# v4MetroKnome.net
KiCad netlist of a schematic drawn in EAGLE
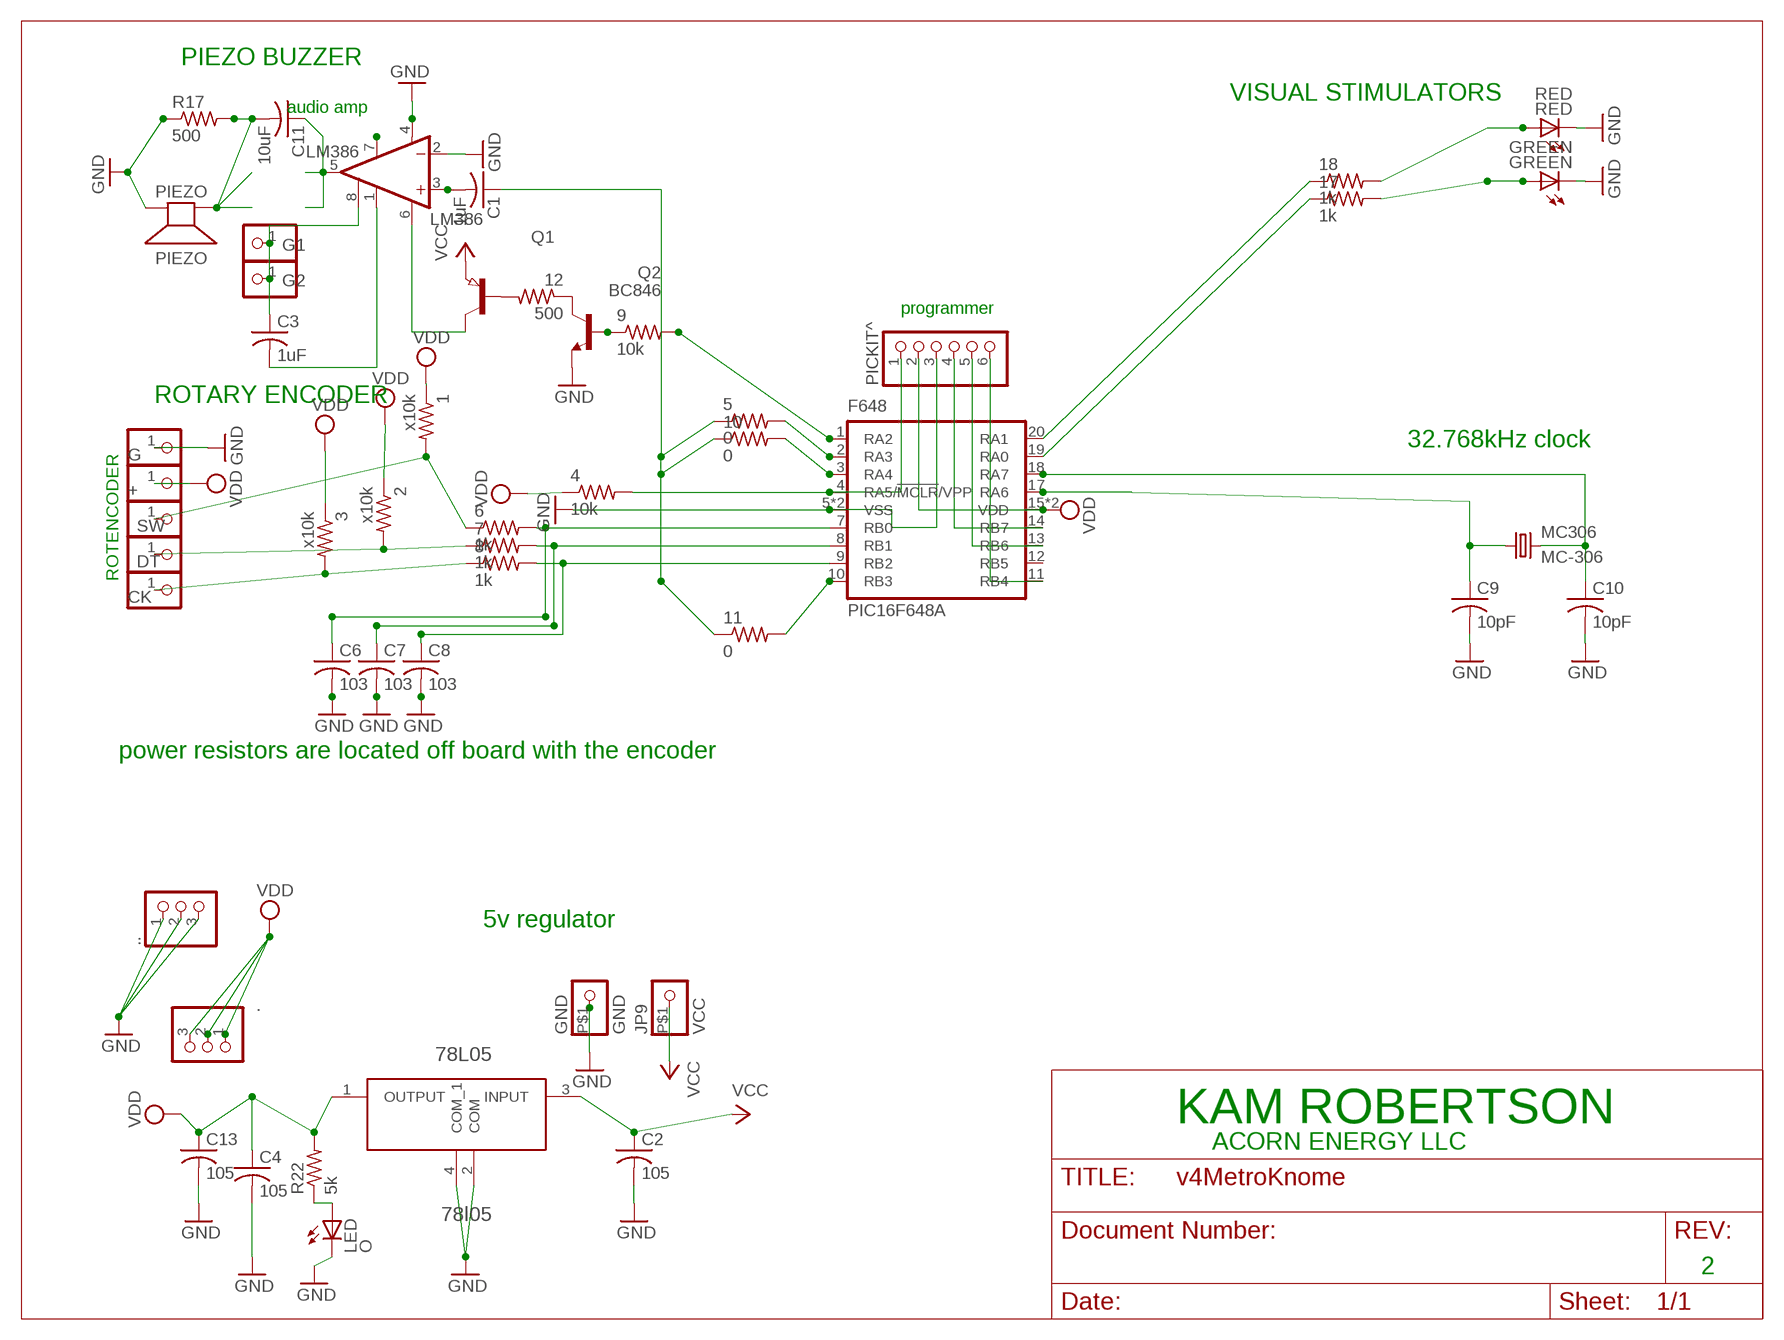
[diagram p0: schematic, sheet 1]

(export (version "E")
  (design (tool "Eeschema 10.0.6"))
  (components
    (comp (ref "+")
      (value "PINHD-1X1CB")
      (footprint "eagle-import:1X01-CLEANBIG")
      (libsource (lib "eagle-import") (part "PINHD-1X1CB"))
    )
    (comp (ref ".")
      (value "PINHD-1X3CB")
      (footprint "eagle-import:1X03-CLEANBIG")
      (libsource (lib "eagle-import") (part "PINHD-1X3CB"))
    )
    (comp (ref "..")
      (value "PINHD-1X3CB")
      (footprint "eagle-import:1X03-CLEANBIG")
      (libsource (lib "eagle-import") (part "PINHD-1X3CB"))
    )
    (comp (ref "1")
      (value "x10k")
      (footprint "eagle-import:R1206")
      (libsource (lib "eagle-import") (part "R-US_R1206"))
    )
    (comp (ref "2")
      (value "x10k")
      (footprint "eagle-import:R1206")
      (libsource (lib "eagle-import") (part "R-US_R1206"))
    )
    (comp (ref "3")
      (value "x10k")
      (footprint "eagle-import:R1206")
      (libsource (lib "eagle-import") (part "R-US_R1206"))
    )
    (comp (ref "4")
      (value "10k")
      (footprint "eagle-import:R1206")
      (libsource (lib "eagle-import") (part "R-US_R1206"))
    )
    (comp (ref "5")
      (value "0")
      (footprint "eagle-import:R1206")
      (libsource (lib "eagle-import") (part "R-US_R1206"))
    )
    (comp (ref "6")
      (value "1k")
      (footprint "eagle-import:R1206")
      (libsource (lib "eagle-import") (part "R-US_R1206"))
    )
    (comp (ref "7")
      (value "1k")
      (footprint "eagle-import:R1206")
      (libsource (lib "eagle-import") (part "R-US_R1206"))
    )
    (comp (ref "8")
      (value "1k")
      (footprint "eagle-import:R1206")
      (libsource (lib "eagle-import") (part "R-US_R1206"))
    )
    (comp (ref "9")
      (value "10k")
      (footprint "eagle-import:R1206")
      (libsource (lib "eagle-import") (part "R-US_R1206"))
    )
    (comp (ref "10")
      (value "0")
      (footprint "eagle-import:R1206")
      (libsource (lib "eagle-import") (part "R-US_R1206"))
    )
    (comp (ref "11")
      (value "0")
      (footprint "eagle-import:R1206")
      (libsource (lib "eagle-import") (part "R-US_R1206"))
    )
    (comp (ref "12")
      (value "500")
      (footprint "eagle-import:R1206")
      (libsource (lib "eagle-import") (part "R-US_R1206"))
    )
    (comp (ref "17")
      (value "1k")
      (footprint "eagle-import:R1206")
      (libsource (lib "eagle-import") (part "R-US_R1206"))
    )
    (comp (ref "18")
      (value "1k")
      (footprint "eagle-import:R1206")
      (libsource (lib "eagle-import") (part "R-US_R1206"))
    )
    (comp (ref "78L05")
      (value "78l05")
      (footprint "eagle-import:SOT150P400X160-4N")
      (fields (field (name "MPN") "UA78L05ACPKG3"))
      (libsource (lib "eagle-import") (part "UA78L05ACPKG3"))
    )
    (comp (ref "C1")
      (value "1uF")
      (footprint "eagle-import:C1210")
      (libsource (lib "eagle-import") (part "C-USC1210"))
    )
    (comp (ref "C2")
      (value "105")
      (footprint "eagle-import:C1210")
      (libsource (lib "eagle-import") (part "C-USC1210"))
    )
    (comp (ref "C3")
      (value "1uF")
      (footprint "eagle-import:C1210")
      (libsource (lib "eagle-import") (part "C-USC1210"))
    )
    (comp (ref "C4")
      (value "105")
      (footprint "eagle-import:C1210")
      (libsource (lib "eagle-import") (part "C-USC1210"))
    )
    (comp (ref "C6")
      (value "103")
      (footprint "eagle-import:C1210")
      (libsource (lib "eagle-import") (part "C-USC1210"))
    )
    (comp (ref "C7")
      (value "103")
      (footprint "eagle-import:C1210")
      (libsource (lib "eagle-import") (part "C-USC1210"))
    )
    (comp (ref "C8")
      (value "103")
      (footprint "eagle-import:C1210")
      (libsource (lib "eagle-import") (part "C-USC1210"))
    )
    (comp (ref "C9")
      (value "10pF")
      (footprint "eagle-import:C1210")
      (libsource (lib "eagle-import") (part "C-USC1210"))
    )
    (comp (ref "C10")
      (value "10pF")
      (footprint "eagle-import:C1210")
      (libsource (lib "eagle-import") (part "C-USC1210"))
    )
    (comp (ref "C11")
      (value "10uF")
      (footprint "eagle-import:C1210")
      (libsource (lib "eagle-import") (part "C-USC1210"))
    )
    (comp (ref "C13")
      (value "105")
      (footprint "eagle-import:C1210")
      (libsource (lib "eagle-import") (part "C-USC1210"))
    )
    (comp (ref "CK")
      (value "PINHD-1X1CB")
      (footprint "eagle-import:1X01-CLEANBIG")
      (libsource (lib "eagle-import") (part "PINHD-1X1CB"))
    )
    (comp (ref "DT")
      (value "PINHD-1X1CB")
      (footprint "eagle-import:1X01-CLEANBIG")
      (libsource (lib "eagle-import") (part "PINHD-1X1CB"))
    )
    (comp (ref "F648")
      (value "PIC16F648A")
      (footprint "eagle-import:SSOP20")
      (libsource (lib "eagle-import") (part "PIC16F1826/27SS"))
    )
    (comp (ref "G")
      (value "PINHD-1X1CB")
      (footprint "eagle-import:1X01-CLEANBIG")
      (libsource (lib "eagle-import") (part "PINHD-1X1CB"))
    )
    (comp (ref "G1")
      (value "PINHD-1X1CB")
      (footprint "eagle-import:1X01-CLEANBIG")
      (libsource (lib "eagle-import") (part "PINHD-1X1CB"))
    )
    (comp (ref "G2")
      (value "PINHD-1X1CB")
      (footprint "eagle-import:1X01-CLEANBIG")
      (libsource (lib "eagle-import") (part "PINHD-1X1CB"))
    )
    (comp (ref "GND")
      (value "GND")
      (footprint "eagle-import:1X1-BIGPOGO")
      (libsource (lib "eagle-import") (part "PINHD-1X1-BIGPOGO"))
    )
    (comp (ref "GREEN")
      (value "GREEN")
      (footprint "eagle-import:LED5MM")
      (libsource (lib "eagle-import") (part "LED5MM"))
    )
    (comp (ref "JP9")
      (value "VCC")
      (footprint "eagle-import:1X1-BIGPOGO")
      (libsource (lib "eagle-import") (part "PINHD-1X1-BIGPOGO"))
    )
    (comp (ref "LED")
      (value "O")
      (footprint "eagle-import:CHIPLED_1206")
      (libsource (lib "eagle-import") (part "LEDCHIPLED_1206"))
    )
    (comp (ref "LM386")
      (value "LM386")
      (footprint "eagle-import:SO08")
      (libsource (lib "eagle-import") (part "LM386?-M1"))
    )
    (comp (ref "MC306")
      (value "MC-306")
      (footprint "eagle-import:MC-306")
      (fields
        (field (name "MPN") "MC-306 60.0KHZ  100PPM ,12.5PF")
        (field (name "MPN_1") "MC-306 60.0KHZ  100PPM ,12.5PF")
        (field (name "OC_FARNELL") "1278040")
        (field (name "OC_NEWARK") "31M5576")
      )
      (libsource (lib "eagle-import") (part "MC-306"))
    )
    (comp (ref "PICKIT^")
      (value "PINHD-1X6LOCK")
      (footprint "eagle-import:1X06-BIGLOCK")
      (libsource (lib "eagle-import") (part "PINHD-1X6LOCK"))
    )
    (comp (ref "PIEZO")
      (value "PIEZO")
      (footprint "eagle-import:PS12")
      (libsource (lib "eagle-import") (part "SPEAKER/PS12"))
    )
    (comp (ref "Q1")
      (value "PNP-TRANSISTOR_SOT89")
      (footprint "eagle-import:SOT89")
      (libsource (lib "eagle-import") (part "PNP-TRANSISTOR_SOT89"))
    )
    (comp (ref "Q2")
      (value "BC846")
      (footprint "eagle-import:SOT23")
      (libsource (lib "eagle-import") (part "BC846"))
    )
    (comp (ref "R17")
      (value "500")
      (footprint "eagle-import:R1206")
      (libsource (lib "eagle-import") (part "R-US_R1206"))
    )
    (comp (ref "R22")
      (value "5k")
      (footprint "eagle-import:R1206")
      (libsource (lib "eagle-import") (part "R-US_R1206"))
    )
    (comp (ref "RED")
      (value "RED")
      (footprint "eagle-import:LED5MM")
      (libsource (lib "eagle-import") (part "LED5MM"))
    )
    (comp (ref "SW")
      (value "PINHD-1X1CB")
      (footprint "eagle-import:1X01-CLEANBIG")
      (libsource (lib "eagle-import") (part "PINHD-1X1CB"))
    )
  )
  (nets
    (net (code "1") (name "GND") (class "Default")
      (node (ref "..") (pin "1") (pinfunction "1_1") (pintype "passive"))
      (node (ref "..") (pin "2") (pinfunction "2_2") (pintype "passive"))
      (node (ref "..") (pin "3") (pinfunction "3_3") (pintype "passive"))
      (node (ref "78L05") (pin "2") (pinfunction "COM_2") (pintype "power_in"))
      (node (ref "78L05") (pin "4") (pinfunction "COM_1_4") (pintype "power_in"))
      (node (ref "C10") (pin "2") (pinfunction "2_2") (pintype "passive"))
      (node (ref "C13") (pin "2") (pinfunction "2_2") (pintype "passive"))
      (node (ref "C2") (pin "2") (pinfunction "2_2") (pintype "passive"))
      (node (ref "C4") (pin "2") (pinfunction "2_2") (pintype "passive"))
      (node (ref "C6") (pin "2") (pinfunction "2_2") (pintype "passive"))
      (node (ref "C7") (pin "2") (pinfunction "2_2") (pintype "passive"))
      (node (ref "C8") (pin "2") (pinfunction "2_2") (pintype "passive"))
      (node (ref "C9") (pin "2") (pinfunction "2_2") (pintype "passive"))
      (node (ref "F648") (pin "5") (pinfunction "VSS_5") (pintype "power_in"))
      (node (ref "F648") (pin "6") (pinfunction "VSS_6") (pintype "power_in"))
      (node (ref "G") (pin "1") (pinfunction "1_1") (pintype "passive"))
      (node (ref "GND") (pin "P$1") (pinfunction "1_P$1") (pintype "passive"))
      (node (ref "GREEN") (pin "K") (pinfunction "C_K") (pintype "passive"))
      (node (ref "LED") (pin "C") (pinfunction "C_C") (pintype "passive"))
      (node (ref "LM386") (pin "2") (pinfunction "-IN_2") (pintype "input"))
      (node (ref "LM386") (pin "4") (pinfunction "GND_4") (pintype "power_in"))
      (node (ref "PICKIT^") (pin "3") (pinfunction "3_3") (pintype "passive"))
      (node (ref "PIEZO") (pin "P$2") (pinfunction "-_P$2") (pintype "passive"))
      (node (ref "Q2") (pin "2") (pinfunction "E_2") (pintype "passive"))
      (node (ref "R17") (pin "1") (pinfunction "1_1") (pintype "passive"))
      (node (ref "RED") (pin "K") (pinfunction "C_K") (pintype "passive"))
    )
    (net (code "2") (name "Net-(1-Pad2)") (class "Default")
      (node (ref "1") (pin "2") (pinfunction "2_2") (pintype "passive"))
      (node (ref "6") (pin "1") (pinfunction "1_1") (pintype "passive"))
      (node (ref "SW") (pin "1") (pinfunction "1_1") (pintype "passive"))
    )
    (net (code "3") (name "Net-(2-Pad2)") (class "Default")
      (node (ref "2") (pin "2") (pinfunction "2_2") (pintype "passive"))
      (node (ref "7") (pin "1") (pinfunction "1_1") (pintype "passive"))
      (node (ref "DT") (pin "1") (pinfunction "1_1") (pintype "passive"))
    )
    (net (code "4") (name "Net-(3-Pad2)") (class "Default")
      (node (ref "3") (pin "2") (pinfunction "2_2") (pintype "passive"))
      (node (ref "8") (pin "1") (pinfunction "1_1") (pintype "passive"))
      (node (ref "CK") (pin "1") (pinfunction "1_1") (pintype "passive"))
    )
    (net (code "5") (name "Net-(10-Pad1)") (class "Default")
      (node (ref "10") (pin "1") (pinfunction "1_1") (pintype "passive"))
      (node (ref "11") (pin "1") (pinfunction "1_1") (pintype "passive"))
      (node (ref "5") (pin "1") (pinfunction "1_1") (pintype "passive"))
      (node (ref "C1") (pin "1") (pinfunction "1_1") (pintype "passive"))
    )
    (net (code "6") (name "Net-(17-Pad2)") (class "Default")
      (node (ref "17") (pin "2") (pinfunction "2_2") (pintype "passive"))
      (node (ref "GREEN") (pin "A") (pinfunction "A_A") (pintype "passive"))
    )
    (net (code "7") (name "Net-(18-Pad2)") (class "Default")
      (node (ref "18") (pin "2") (pinfunction "2_2") (pintype "passive"))
      (node (ref "RED") (pin "A") (pinfunction "A_A") (pintype "passive"))
    )
    (net (code "8") (name "Net-(C3-Pad1)") (class "Default")
      (node (ref "C3") (pin "1") (pinfunction "1_1") (pintype "passive"))
      (node (ref "G1") (pin "1") (pinfunction "1_1") (pintype "passive"))
      (node (ref "G2") (pin "1") (pinfunction "1_1") (pintype "passive"))
      (node (ref "LM386") (pin "8") (pinfunction "GAIN_8") (pintype "passive"))
    )
    (net (code "9") (name "Net-(C3-Pad2)") (class "Default")
      (node (ref "C3") (pin "2") (pinfunction "2_2") (pintype "passive"))
      (node (ref "LM386") (pin "1") (pinfunction "GAIN_1") (pintype "passive"))
    )
    (net (code "10") (name "Net-(F648-RA0)") (class "Default")
      (node (ref "17") (pin "1") (pinfunction "1_1") (pintype "passive"))
      (node (ref "F648") (pin "19") (pinfunction "RA0_19") (pintype "bidirectional"))
    )
    (net (code "11") (name "Net-(F648-RA1)") (class "Default")
      (node (ref "18") (pin "1") (pinfunction "1_1") (pintype "passive"))
      (node (ref "F648") (pin "20") (pinfunction "RA1_20") (pintype "bidirectional"))
    )
    (net (code "12") (name "Net-(F648-RA2)") (class "Default")
      (node (ref "9") (pin "2") (pinfunction "2_2") (pintype "passive"))
      (node (ref "F648") (pin "1") (pinfunction "RA2_1") (pintype "bidirectional"))
    )
    (net (code "13") (name "Net-(F648-RA3)") (class "Default")
      (node (ref "5") (pin "2") (pinfunction "2_2") (pintype "passive"))
      (node (ref "F648") (pin "2") (pinfunction "RA3_2") (pintype "bidirectional"))
    )
    (net (code "14") (name "Net-(F648-RA4)") (class "Default")
      (node (ref "10") (pin "2") (pinfunction "2_2") (pintype "passive"))
      (node (ref "F648") (pin "3") (pinfunction "RA4_3") (pintype "bidirectional"))
    )
    (net (code "15") (name "Net-(F648-RA5{slash}~{MCLR}{slash}VPP)") (class "Default")
      (node (ref "4") (pin "2") (pinfunction "2_2") (pintype "passive"))
      (node (ref "F648") (pin "4") (pinfunction "RA5/~{MCLR}/VPP_4") (pintype "bidirectional"))
      (node (ref "PICKIT^") (pin "1") (pinfunction "1_1") (pintype "passive"))
    )
    (net (code "16") (name "Net-(F648-RA6)") (class "Default")
      (node (ref "C9") (pin "1") (pinfunction "1_1") (pintype "passive"))
      (node (ref "F648") (pin "17") (pinfunction "RA6_17") (pintype "bidirectional"))
      (node (ref "MC306") (pin "1") (pinfunction "1_1") (pintype "passive"))
    )
    (net (code "17") (name "Net-(F648-RA7)") (class "Default")
      (node (ref "C10") (pin "1") (pinfunction "1_1") (pintype "passive"))
      (node (ref "F648") (pin "18") (pinfunction "RA7_18") (pintype "bidirectional"))
      (node (ref "MC306") (pin "4") (pinfunction "2_4") (pintype "passive"))
    )
    (net (code "18") (name "Net-(F648-RB0)") (class "Default")
      (node (ref "6") (pin "2") (pinfunction "2_2") (pintype "passive"))
      (node (ref "C6") (pin "1") (pinfunction "1_1") (pintype "passive"))
      (node (ref "F648") (pin "7") (pinfunction "RB0_7") (pintype "bidirectional"))
    )
    (net (code "19") (name "Net-(F648-RB1)") (class "Default")
      (node (ref "7") (pin "2") (pinfunction "2_2") (pintype "passive"))
      (node (ref "C7") (pin "1") (pinfunction "1_1") (pintype "passive"))
      (node (ref "F648") (pin "8") (pinfunction "RB1_8") (pintype "bidirectional"))
    )
    (net (code "20") (name "Net-(F648-RB2)") (class "Default")
      (node (ref "8") (pin "2") (pinfunction "2_2") (pintype "passive"))
      (node (ref "C8") (pin "1") (pinfunction "1_1") (pintype "passive"))
      (node (ref "F648") (pin "9") (pinfunction "RB2_9") (pintype "bidirectional"))
    )
    (net (code "21") (name "Net-(F648-RB3)") (class "Default")
      (node (ref "11") (pin "2") (pinfunction "2_2") (pintype "passive"))
      (node (ref "F648") (pin "10") (pinfunction "RB3_10") (pintype "bidirectional"))
    )
    (net (code "22") (name "Net-(F648-RB4)") (class "Default")
      (node (ref "F648") (pin "11") (pinfunction "RB4_11") (pintype "bidirectional"))
      (node (ref "PICKIT^") (pin "6") (pinfunction "6_6") (pintype "passive"))
    )
    (net (code "23") (name "Net-(F648-RB6)") (class "Default")
      (node (ref "F648") (pin "13") (pinfunction "RB6_13") (pintype "bidirectional"))
      (node (ref "PICKIT^") (pin "5") (pinfunction "5_5") (pintype "passive"))
    )
    (net (code "24") (name "Net-(F648-RB7)") (class "Default")
      (node (ref "F648") (pin "14") (pinfunction "RB7_14") (pintype "bidirectional"))
      (node (ref "PICKIT^") (pin "4") (pinfunction "4_4") (pintype "passive"))
    )
    (net (code "25") (name "Net-(LED-PadA)") (class "Default")
      (node (ref "LED") (pin "A") (pinfunction "A_A") (pintype "passive"))
      (node (ref "R22") (pin "1") (pinfunction "1_1") (pintype "passive"))
    )
    (net (code "26") (name "Net-(LM386-+IN)") (class "Default")
      (node (ref "C1") (pin "2") (pinfunction "2_2") (pintype "passive"))
      (node (ref "LM386") (pin "3") (pinfunction "+IN_3") (pintype "input"))
    )
    (net (code "27") (name "Net-(LM386-OUT)") (class "Default")
      (node (ref "C11") (pin "1") (pinfunction "1_1") (pintype "passive"))
      (node (ref "LM386") (pin "5") (pinfunction "OUT_5") (pintype "output"))
    )
    (net (code "28") (name "Net-(LM386-VS)") (class "Default")
      (node (ref "LM386") (pin "6") (pinfunction "VS_6") (pintype "power_in"))
      (node (ref "Q1") (pin "2") (pinfunction "C_2") (pintype "passive"))
    )
    (net (code "29") (name "Net-(PIEZO-+)") (class "Default")
      (node (ref "C11") (pin "2") (pinfunction "2_2") (pintype "passive"))
      (node (ref "PIEZO") (pin "P$1") (pinfunction "+_P$1") (pintype "passive"))
      (node (ref "R17") (pin "2") (pinfunction "2_2") (pintype "passive"))
    )
    (net (code "30") (name "Net-(Q1-B)") (class "Default")
      (node (ref "12") (pin "2") (pinfunction "2_2") (pintype "passive"))
      (node (ref "Q1") (pin "1") (pinfunction "B_1") (pintype "passive"))
    )
    (net (code "31") (name "Net-(Q2-B)") (class "Default")
      (node (ref "9") (pin "1") (pinfunction "1_1") (pintype "passive"))
      (node (ref "Q2") (pin "1") (pinfunction "B_1") (pintype "passive"))
    )
    (net (code "32") (name "Net-(Q2-C)") (class "Default")
      (node (ref "12") (pin "1") (pinfunction "1_1") (pintype "passive"))
      (node (ref "Q2") (pin "3") (pinfunction "C_3") (pintype "passive"))
    )
    (net (code "33") (name "VCC") (class "Default")
      (node (ref "78L05") (pin "3") (pinfunction "INPUT_3") (pintype "input"))
      (node (ref "C2") (pin "1") (pinfunction "1_1") (pintype "passive"))
      (node (ref "JP9") (pin "P$1") (pinfunction "1_P$1") (pintype "passive"))
      (node (ref "Q1") (pin "3") (pinfunction "E_3") (pintype "passive"))
    )
    (net (code "34") (name "VDD") (class "Default")
      (node (ref "+") (pin "1") (pinfunction "1_1") (pintype "passive"))
      (node (ref ".") (pin "1") (pinfunction "1_1") (pintype "passive"))
      (node (ref ".") (pin "2") (pinfunction "2_2") (pintype "passive"))
      (node (ref ".") (pin "3") (pinfunction "3_3") (pintype "passive"))
      (node (ref "1") (pin "1") (pinfunction "1_1") (pintype "passive"))
      (node (ref "2") (pin "1") (pinfunction "1_1") (pintype "passive"))
      (node (ref "3") (pin "1") (pinfunction "1_1") (pintype "passive"))
      (node (ref "4") (pin "1") (pinfunction "1_1") (pintype "passive"))
      (node (ref "78L05") (pin "1") (pinfunction "OUTPUT_1") (pintype "output"))
      (node (ref "C13") (pin "1") (pinfunction "1_1") (pintype "passive"))
      (node (ref "C4") (pin "1") (pinfunction "1_1") (pintype "passive"))
      (node (ref "F648") (pin "15") (pinfunction "VDD_15") (pintype "power_in"))
      (node (ref "F648") (pin "16") (pinfunction "VDD_16") (pintype "power_in"))
      (node (ref "PICKIT^") (pin "2") (pinfunction "2_2") (pintype "passive"))
      (node (ref "R22") (pin "2") (pinfunction "2_2") (pintype "passive"))
    )
    (net (code "35") (name "unconnected-(F648-RB5-Pad12)") (class "Default")
      (node (ref "F648") (pin "12") (pinfunction "RB5_12") (pintype "bidirectional"))
    )
    (net (code "36") (name "unconnected-(LM386-BYPASS-Pad7)") (class "Default")
      (node (ref "LM386") (pin "7") (pinfunction "BYPASS_7") (pintype "passive"))
    )
  )
)
